# Keys.net
KiCad netlist of a schematic drawn in Altium Designer
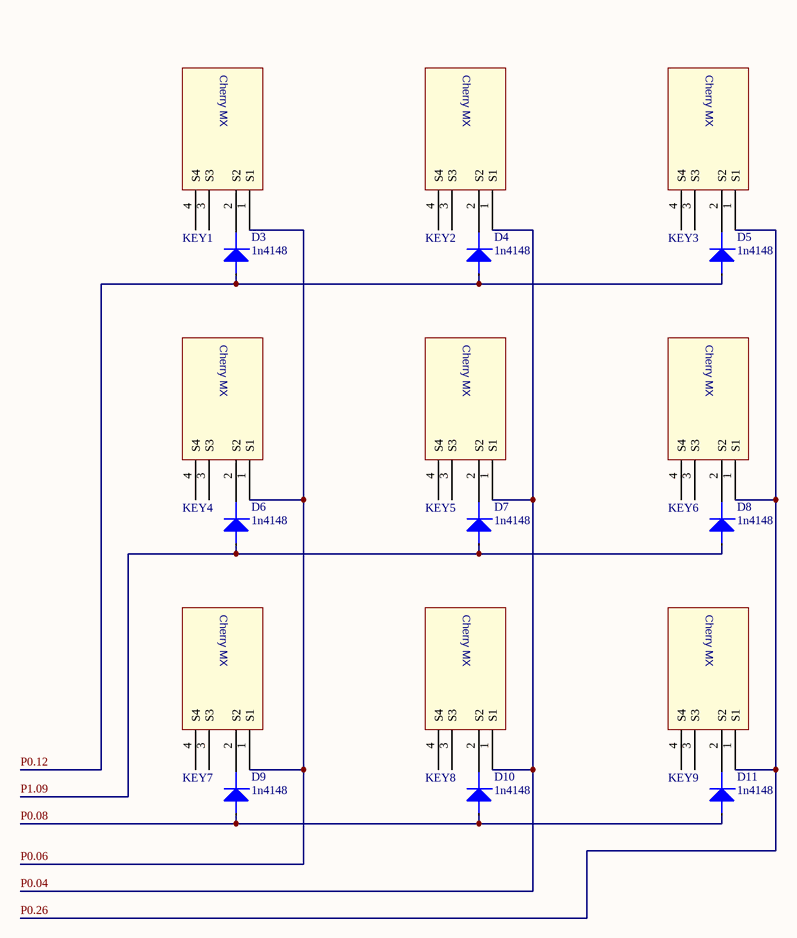
[diagram p0: Keys.SchDoc]

(export (version "E")
  (design (tool "Eeschema 10.0.6"))
  (components
    (comp (ref "D3")
      (value "1n4148")
      (footprint "SOD-123")
      (description "Zener Diode")
      (libsource (lib "二极管") (part "ZENER3"))
    )
    (comp (ref "D4")
      (value "1n4148")
      (footprint "SOD-123")
      (description "Zener Diode")
      (libsource (lib "二极管") (part "ZENER3"))
    )
    (comp (ref "D5")
      (value "1n4148")
      (footprint "SOD-123")
      (description "Zener Diode")
      (libsource (lib "二极管") (part "ZENER3"))
    )
    (comp (ref "D6")
      (value "1n4148")
      (footprint "SOD-123")
      (description "Zener Diode")
      (libsource (lib "二极管") (part "ZENER3"))
    )
    (comp (ref "D7")
      (value "1n4148")
      (footprint "SOD-123")
      (description "Zener Diode")
      (libsource (lib "二极管") (part "ZENER3"))
    )
    (comp (ref "D8")
      (value "1n4148")
      (footprint "SOD-123")
      (description "Zener Diode")
      (libsource (lib "二极管") (part "ZENER3"))
    )
    (comp (ref "D9")
      (value "1n4148")
      (footprint "SOD-123")
      (description "Zener Diode")
      (libsource (lib "二极管") (part "ZENER3"))
    )
    (comp (ref "D10")
      (value "1n4148")
      (footprint "SOD-123")
      (description "Zener Diode")
      (libsource (lib "二极管") (part "ZENER3"))
    )
    (comp (ref "D11")
      (value "1n4148")
      (footprint "SOD-123")
      (description "Zener Diode")
      (libsource (lib "二极管") (part "ZENER3"))
    )
    (comp (ref "KEY1")
      (value "CHERRY_MX")
      (footprint "CHERRYMX")
      (libsource (lib "Fsociety_Keyboard") (part "CHERRY_MX"))
    )
    (comp (ref "KEY2")
      (value "CHERRY_MX")
      (footprint "CHERRYMX")
      (libsource (lib "Fsociety_Keyboard") (part "CHERRY_MX"))
    )
    (comp (ref "KEY3")
      (value "CHERRY_MX")
      (footprint "CHERRYMX")
      (libsource (lib "Fsociety_Keyboard") (part "CHERRY_MX"))
    )
    (comp (ref "KEY4")
      (value "CHERRY_MX")
      (footprint "CHERRYMX")
      (libsource (lib "Fsociety_Keyboard") (part "CHERRY_MX"))
    )
    (comp (ref "KEY5")
      (value "CHERRY_MX")
      (footprint "CHERRYMX")
      (libsource (lib "Fsociety_Keyboard") (part "CHERRY_MX"))
    )
    (comp (ref "KEY6")
      (value "CHERRY_MX")
      (footprint "CHERRYMX")
      (libsource (lib "Fsociety_Keyboard") (part "CHERRY_MX"))
    )
    (comp (ref "KEY7")
      (value "CHERRY_MX")
      (footprint "CHERRYMX")
      (libsource (lib "Fsociety_Keyboard") (part "CHERRY_MX"))
    )
    (comp (ref "KEY8")
      (value "CHERRY_MX")
      (footprint "CHERRYMX")
      (libsource (lib "Fsociety_Keyboard") (part "CHERRY_MX"))
    )
    (comp (ref "KEY9")
      (value "CHERRY_MX")
      (footprint "CHERRYMX")
      (libsource (lib "Fsociety_Keyboard") (part "CHERRY_MX"))
    )
  )
  (nets
    (net (code "1") (name "/P0.04") (class "Default")
      (node (ref "KEY2") (pin "1") (pinfunction "S1_1") (pintype "passive"))
      (node (ref "KEY5") (pin "1") (pinfunction "S1_1") (pintype "passive"))
      (node (ref "KEY8") (pin "1") (pinfunction "S1_1") (pintype "passive"))
    )
    (net (code "2") (name "/P0.06") (class "Default")
      (node (ref "KEY1") (pin "1") (pinfunction "S1_1") (pintype "passive"))
      (node (ref "KEY4") (pin "1") (pinfunction "S1_1") (pintype "passive"))
      (node (ref "KEY7") (pin "1") (pinfunction "S1_1") (pintype "passive"))
    )
    (net (code "3") (name "/P0.08") (class "Default")
      (node (ref "D10") (pin "1") (pinfunction "A_1") (pintype "passive"))
      (node (ref "D11") (pin "1") (pinfunction "A_1") (pintype "passive"))
      (node (ref "D9") (pin "1") (pinfunction "A_1") (pintype "passive"))
    )
    (net (code "4") (name "/P0.12") (class "Default")
      (node (ref "D3") (pin "1") (pinfunction "A_1") (pintype "passive"))
      (node (ref "D4") (pin "1") (pinfunction "A_1") (pintype "passive"))
      (node (ref "D5") (pin "1") (pinfunction "A_1") (pintype "passive"))
    )
    (net (code "5") (name "/P0.26") (class "Default")
      (node (ref "KEY3") (pin "1") (pinfunction "S1_1") (pintype "passive"))
      (node (ref "KEY6") (pin "1") (pinfunction "S1_1") (pintype "passive"))
      (node (ref "KEY9") (pin "1") (pinfunction "S1_1") (pintype "passive"))
    )
    (net (code "6") (name "/P1.09") (class "Default")
      (node (ref "D6") (pin "1") (pinfunction "A_1") (pintype "passive"))
      (node (ref "D7") (pin "1") (pinfunction "A_1") (pintype "passive"))
      (node (ref "D8") (pin "1") (pinfunction "A_1") (pintype "passive"))
    )
    (net (code "7") (name "Net-(D3-K)") (class "Default")
      (node (ref "D3") (pin "2") (pinfunction "K_2") (pintype "passive"))
      (node (ref "KEY1") (pin "2") (pinfunction "S2_2") (pintype "passive"))
    )
    (net (code "8") (name "Net-(D4-K)") (class "Default")
      (node (ref "D4") (pin "2") (pinfunction "K_2") (pintype "passive"))
      (node (ref "KEY2") (pin "2") (pinfunction "S2_2") (pintype "passive"))
    )
    (net (code "9") (name "Net-(D5-K)") (class "Default")
      (node (ref "D5") (pin "2") (pinfunction "K_2") (pintype "passive"))
      (node (ref "KEY3") (pin "2") (pinfunction "S2_2") (pintype "passive"))
    )
    (net (code "10") (name "Net-(D6-K)") (class "Default")
      (node (ref "D6") (pin "2") (pinfunction "K_2") (pintype "passive"))
      (node (ref "KEY4") (pin "2") (pinfunction "S2_2") (pintype "passive"))
    )
    (net (code "11") (name "Net-(D7-K)") (class "Default")
      (node (ref "D7") (pin "2") (pinfunction "K_2") (pintype "passive"))
      (node (ref "KEY5") (pin "2") (pinfunction "S2_2") (pintype "passive"))
    )
    (net (code "12") (name "Net-(D8-K)") (class "Default")
      (node (ref "D8") (pin "2") (pinfunction "K_2") (pintype "passive"))
      (node (ref "KEY6") (pin "2") (pinfunction "S2_2") (pintype "passive"))
    )
    (net (code "13") (name "Net-(D9-K)") (class "Default")
      (node (ref "D9") (pin "2") (pinfunction "K_2") (pintype "passive"))
      (node (ref "KEY7") (pin "2") (pinfunction "S2_2") (pintype "passive"))
    )
    (net (code "14") (name "Net-(D10-K)") (class "Default")
      (node (ref "D10") (pin "2") (pinfunction "K_2") (pintype "passive"))
      (node (ref "KEY8") (pin "2") (pinfunction "S2_2") (pintype "passive"))
    )
    (net (code "15") (name "Net-(D11-K)") (class "Default")
      (node (ref "D11") (pin "2") (pinfunction "K_2") (pintype "passive"))
      (node (ref "KEY9") (pin "2") (pinfunction "S2_2") (pintype "passive"))
    )
    (net (code "16") (name "unconnected-(KEY1-S3-Pad3)") (class "Default")
      (node (ref "KEY1") (pin "3") (pinfunction "S3_3") (pintype "passive"))
    )
    (net (code "17") (name "unconnected-(KEY1-S4-Pad4)") (class "Default")
      (node (ref "KEY1") (pin "4") (pinfunction "S4_4") (pintype "passive"))
    )
    (net (code "18") (name "unconnected-(KEY2-S3-Pad3)") (class "Default")
      (node (ref "KEY2") (pin "3") (pinfunction "S3_3") (pintype "passive"))
    )
    (net (code "19") (name "unconnected-(KEY2-S4-Pad4)") (class "Default")
      (node (ref "KEY2") (pin "4") (pinfunction "S4_4") (pintype "passive"))
    )
    (net (code "20") (name "unconnected-(KEY3-S3-Pad3)") (class "Default")
      (node (ref "KEY3") (pin "3") (pinfunction "S3_3") (pintype "passive"))
    )
    (net (code "21") (name "unconnected-(KEY3-S4-Pad4)") (class "Default")
      (node (ref "KEY3") (pin "4") (pinfunction "S4_4") (pintype "passive"))
    )
    (net (code "22") (name "unconnected-(KEY4-S3-Pad3)") (class "Default")
      (node (ref "KEY4") (pin "3") (pinfunction "S3_3") (pintype "passive"))
    )
    (net (code "23") (name "unconnected-(KEY4-S4-Pad4)") (class "Default")
      (node (ref "KEY4") (pin "4") (pinfunction "S4_4") (pintype "passive"))
    )
    (net (code "24") (name "unconnected-(KEY5-S3-Pad3)") (class "Default")
      (node (ref "KEY5") (pin "3") (pinfunction "S3_3") (pintype "passive"))
    )
    (net (code "25") (name "unconnected-(KEY5-S4-Pad4)") (class "Default")
      (node (ref "KEY5") (pin "4") (pinfunction "S4_4") (pintype "passive"))
    )
    (net (code "26") (name "unconnected-(KEY6-S3-Pad3)") (class "Default")
      (node (ref "KEY6") (pin "3") (pinfunction "S3_3") (pintype "passive"))
    )
    (net (code "27") (name "unconnected-(KEY6-S4-Pad4)") (class "Default")
      (node (ref "KEY6") (pin "4") (pinfunction "S4_4") (pintype "passive"))
    )
    (net (code "28") (name "unconnected-(KEY7-S3-Pad3)") (class "Default")
      (node (ref "KEY7") (pin "3") (pinfunction "S3_3") (pintype "passive"))
    )
    (net (code "29") (name "unconnected-(KEY7-S4-Pad4)") (class "Default")
      (node (ref "KEY7") (pin "4") (pinfunction "S4_4") (pintype "passive"))
    )
    (net (code "30") (name "unconnected-(KEY8-S3-Pad3)") (class "Default")
      (node (ref "KEY8") (pin "3") (pinfunction "S3_3") (pintype "passive"))
    )
    (net (code "31") (name "unconnected-(KEY8-S4-Pad4)") (class "Default")
      (node (ref "KEY8") (pin "4") (pinfunction "S4_4") (pintype "passive"))
    )
    (net (code "32") (name "unconnected-(KEY9-S3-Pad3)") (class "Default")
      (node (ref "KEY9") (pin "3") (pinfunction "S3_3") (pintype "passive"))
    )
    (net (code "33") (name "unconnected-(KEY9-S4-Pad4)") (class "Default")
      (node (ref "KEY9") (pin "4") (pinfunction "S4_4") (pintype "passive"))
    )
  )
)
